# DB4100_POW_v0_3.net
KiCad netlist of a schematic drawn in Altium Designer
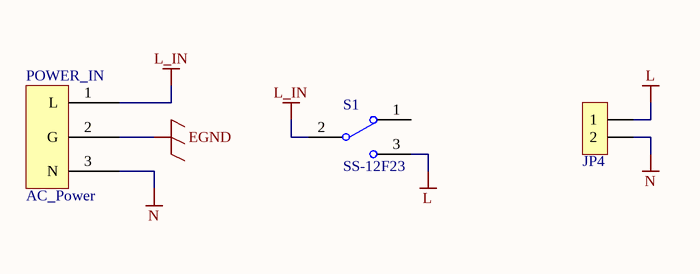
[diagram p0: DB4100_POW_v0.3.SchDoc]

(export (version "E")
  (design (tool "Eeschema 10.0.6"))
  (components
    (comp (ref "JP4")
      (value "HDR-1X2")
      (footprint "VH3.96-3A_2P_R")
      (description "2P接插件")
      (fields (field (name "版权归属") "源创客"))
      (libsource (lib "排针-排母") (part "Header 2"))
    )
    (comp (ref "POWER_IN")
      (value "AC_Power")
      (footprint "POWER_M")
      (description "AC电源插座")
      (libsource (lib "接口类") (part "AC_Power"))
    )
    (comp (ref "S1")
      (value "SS-12F23")
      (footprint "SS11-BBIWJ-R20-R")
      (description "1路波动开关")
      (fields (field (name "版权归属") "源创客"))
      (libsource (lib "开关") (part "SSW-1P"))
    )
  )
  (nets
    (net (code "1") (name "EGND") (class "Default")
      (node (ref "POWER_IN") (pin "2") (pinfunction "G_2") (pintype "passive"))
    )
    (net (code "2") (name "L") (class "Default")
      (node (ref "JP4") (pin "1") (pinfunction "1_1") (pintype "passive"))
      (node (ref "S1") (pin "3") (pinfunction "3_3") (pintype "passive"))
    )
    (net (code "3") (name "L_IN") (class "Default")
      (node (ref "POWER_IN") (pin "1") (pinfunction "L_1") (pintype "passive"))
      (node (ref "S1") (pin "2") (pinfunction "2_2") (pintype "passive"))
    )
    (net (code "4") (name "N") (class "Default")
      (node (ref "JP4") (pin "2") (pinfunction "2_2") (pintype "passive"))
      (node (ref "POWER_IN") (pin "3") (pinfunction "N_3") (pintype "passive"))
    )
    (net (code "5") (name "unconnected-(S1-Pad1)") (class "Default")
      (node (ref "S1") (pin "1") (pinfunction "1_1") (pintype "passive"))
    )
  )
)
